# MICROCONTROLLER.net
KiCad netlist of a schematic drawn in Altium Designer
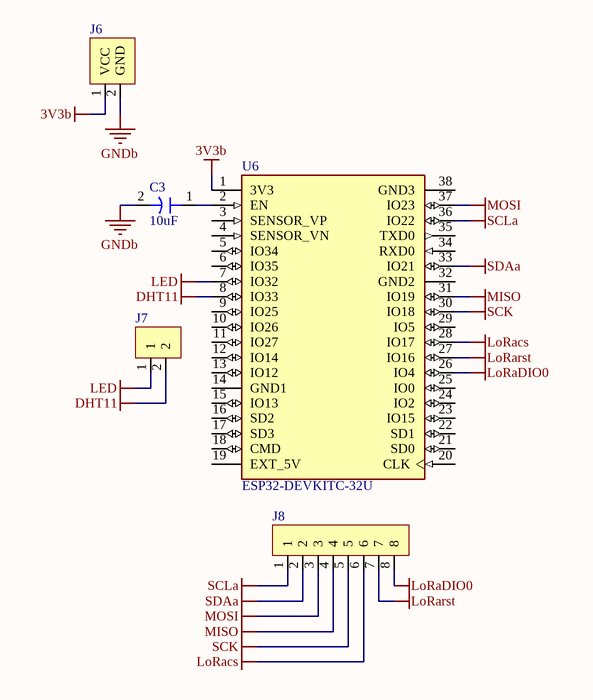
[diagram p0: MICROCONTROLLER.SchDoc]

(export (version "E")
  (design (tool "Eeschema 10.0.6"))
  (components
    (comp (ref "C3")
      (value "10uF")
      (footprint "Electrolytic capacitor 2mm")
      (description "Throug-hole 10uF")
      (libsource (lib "CanSat1_SchLib") (part "E_CAP_10uF"))
    )
    (comp (ref "J6")
      (value "PWR_CONNECTOR")
      (footprint "BATT")
      (description "THT Connector")
      (libsource (lib "CanSat1_SchLib") (part "PWR-CONN"))
    )
    (comp (ref "J7")
      (value "2x1_CONN")
      (footprint "CONN2x1_2.54mm")
      (description "THT 2x1 2.54mm CONN")
      (libsource (lib "CanSat1_SchLib") (part "CONN 2x1"))
    )
    (comp (ref "J8")
      (value "8x1 CONN")
      (footprint "CONN8x1_2.54")
      (description "THT 8x1 2.54mm CONN")
      (libsource (lib "CanSat1_SchLib") (part "CONN 8x1"))
    )
    (comp (ref "U6")
      (value "ESP32-DEVKITC-32U")
      (footprint "MODULE_ESP32-DEVKITC-32U")
      (fields (field (name "MF") "Espressif Systems"))
      (libsource (lib "CanSat1_SchLib") (part "ESP32-DEVKITC-32U"))
    )
  )
  (nets
    (net (code "1") (name "3V3b") (class "Default")
      (node (ref "J6") (pin "1") (pinfunction "VCC_1") (pintype "passive"))
      (node (ref "U6") (pin "1") (pinfunction "3V3_1") (pintype "power_in"))
    )
    (net (code "2") (name "DHT11") (class "Default")
      (node (ref "J7") (pin "2") (pinfunction "2_2") (pintype "passive"))
      (node (ref "U6") (pin "8") (pinfunction "IO33_8") (pintype "bidirectional"))
    )
    (net (code "3") (name "GNDb") (class "Default")
      (node (ref "C3") (pin "2") (pinfunction "-_2") (pintype "passive"))
      (node (ref "J6") (pin "2") (pinfunction "GND_2") (pintype "passive"))
    )
    (net (code "4") (name "LED") (class "Default")
      (node (ref "J7") (pin "1") (pinfunction "1_1") (pintype "passive"))
      (node (ref "U6") (pin "7") (pinfunction "IO32_7") (pintype "bidirectional"))
    )
    (net (code "5") (name "LoRaDIO0") (class "Default")
      (node (ref "J8") (pin "8") (pinfunction "8_8") (pintype "passive"))
      (node (ref "U6") (pin "26") (pinfunction "IO4_26") (pintype "bidirectional"))
    )
    (net (code "6") (name "LoRacs") (class "Default")
      (node (ref "J8") (pin "6") (pinfunction "6_6") (pintype "passive"))
      (node (ref "U6") (pin "28") (pinfunction "IO17_28") (pintype "bidirectional"))
    )
    (net (code "7") (name "LoRarst") (class "Default")
      (node (ref "J8") (pin "7") (pinfunction "7_7") (pintype "passive"))
      (node (ref "U6") (pin "27") (pinfunction "IO16_27") (pintype "bidirectional"))
    )
    (net (code "8") (name "MISO") (class "Default")
      (node (ref "J8") (pin "4") (pinfunction "4_4") (pintype "passive"))
      (node (ref "U6") (pin "31") (pinfunction "IO19_31") (pintype "bidirectional"))
    )
    (net (code "9") (name "MOSI") (class "Default")
      (node (ref "J8") (pin "3") (pinfunction "3_3") (pintype "passive"))
      (node (ref "U6") (pin "37") (pinfunction "IO23_37") (pintype "bidirectional"))
    )
    (net (code "10") (name "Net-(C3-+)") (class "Default")
      (node (ref "C3") (pin "1") (pinfunction "+_1") (pintype "passive"))
      (node (ref "U6") (pin "2") (pinfunction "EN_2") (pintype "input"))
    )
    (net (code "11") (name "SCK") (class "Default")
      (node (ref "J8") (pin "5") (pinfunction "5_5") (pintype "passive"))
      (node (ref "U6") (pin "30") (pinfunction "IO18_30") (pintype "bidirectional"))
    )
    (net (code "12") (name "SCLa") (class "Default")
      (node (ref "J8") (pin "1") (pinfunction "1_1") (pintype "passive"))
      (node (ref "U6") (pin "36") (pinfunction "IO22_36") (pintype "bidirectional"))
    )
    (net (code "13") (name "SDAa") (class "Default")
      (node (ref "J8") (pin "2") (pinfunction "2_2") (pintype "passive"))
      (node (ref "U6") (pin "33") (pinfunction "IO21_33") (pintype "bidirectional"))
    )
    (net (code "14") (name "unconnected-(U6-CLK-Pad20)") (class "Default")
      (node (ref "U6") (pin "20") (pinfunction "CLK_20") (pintype "input"))
    )
    (net (code "15") (name "unconnected-(U6-CMD-Pad18)") (class "Default")
      (node (ref "U6") (pin "18") (pinfunction "CMD_18") (pintype "bidirectional"))
    )
    (net (code "16") (name "unconnected-(U6-EXT_5V-Pad19)") (class "Default")
      (node (ref "U6") (pin "19") (pinfunction "EXT_5V_19") (pintype "power_in"))
    )
    (net (code "17") (name "unconnected-(U6-GND1-Pad14)") (class "Default")
      (node (ref "U6") (pin "14") (pinfunction "GND1_14") (pintype "power_in"))
    )
    (net (code "18") (name "unconnected-(U6-GND2-Pad32)") (class "Default")
      (node (ref "U6") (pin "32") (pinfunction "GND2_32") (pintype "power_in"))
    )
    (net (code "19") (name "unconnected-(U6-GND3-Pad38)") (class "Default")
      (node (ref "U6") (pin "38") (pinfunction "GND3_38") (pintype "power_in"))
    )
    (net (code "20") (name "unconnected-(U6-IO0-Pad25)") (class "Default")
      (node (ref "U6") (pin "25") (pinfunction "IO0_25") (pintype "bidirectional"))
    )
    (net (code "21") (name "unconnected-(U6-IO2-Pad24)") (class "Default")
      (node (ref "U6") (pin "24") (pinfunction "IO2_24") (pintype "bidirectional"))
    )
    (net (code "22") (name "unconnected-(U6-IO5-Pad29)") (class "Default")
      (node (ref "U6") (pin "29") (pinfunction "IO5_29") (pintype "bidirectional"))
    )
    (net (code "23") (name "unconnected-(U6-IO12-Pad13)") (class "Default")
      (node (ref "U6") (pin "13") (pinfunction "IO12_13") (pintype "bidirectional"))
    )
    (net (code "24") (name "unconnected-(U6-IO13-Pad15)") (class "Default")
      (node (ref "U6") (pin "15") (pinfunction "IO13_15") (pintype "bidirectional"))
    )
    (net (code "25") (name "unconnected-(U6-IO14-Pad12)") (class "Default")
      (node (ref "U6") (pin "12") (pinfunction "IO14_12") (pintype "bidirectional"))
    )
    (net (code "26") (name "unconnected-(U6-IO15-Pad23)") (class "Default")
      (node (ref "U6") (pin "23") (pinfunction "IO15_23") (pintype "bidirectional"))
    )
    (net (code "27") (name "unconnected-(U6-IO25-Pad9)") (class "Default")
      (node (ref "U6") (pin "9") (pinfunction "IO25_9") (pintype "bidirectional"))
    )
    (net (code "28") (name "unconnected-(U6-IO26-Pad10)") (class "Default")
      (node (ref "U6") (pin "10") (pinfunction "IO26_10") (pintype "bidirectional"))
    )
    (net (code "29") (name "unconnected-(U6-IO27-Pad11)") (class "Default")
      (node (ref "U6") (pin "11") (pinfunction "IO27_11") (pintype "bidirectional"))
    )
    (net (code "30") (name "unconnected-(U6-IO34-Pad5)") (class "Default")
      (node (ref "U6") (pin "5") (pinfunction "IO34_5") (pintype "bidirectional"))
    )
    (net (code "31") (name "unconnected-(U6-IO35-Pad6)") (class "Default")
      (node (ref "U6") (pin "6") (pinfunction "IO35_6") (pintype "bidirectional"))
    )
    (net (code "32") (name "unconnected-(U6-RXD0-Pad34)") (class "Default")
      (node (ref "U6") (pin "34") (pinfunction "RXD0_34") (pintype "input"))
    )
    (net (code "33") (name "unconnected-(U6-SD0-Pad21)") (class "Default")
      (node (ref "U6") (pin "21") (pinfunction "SD0_21") (pintype "bidirectional"))
    )
    (net (code "34") (name "unconnected-(U6-SD1-Pad22)") (class "Default")
      (node (ref "U6") (pin "22") (pinfunction "SD1_22") (pintype "bidirectional"))
    )
    (net (code "35") (name "unconnected-(U6-SD2-Pad16)") (class "Default")
      (node (ref "U6") (pin "16") (pinfunction "SD2_16") (pintype "bidirectional"))
    )
    (net (code "36") (name "unconnected-(U6-SD3-Pad17)") (class "Default")
      (node (ref "U6") (pin "17") (pinfunction "SD3_17") (pintype "bidirectional"))
    )
    (net (code "37") (name "unconnected-(U6-SENSOR_VN-Pad4)") (class "Default")
      (node (ref "U6") (pin "4") (pinfunction "SENSOR_VN_4") (pintype "input"))
    )
    (net (code "38") (name "unconnected-(U6-SENSOR_VP-Pad3)") (class "Default")
      (node (ref "U6") (pin "3") (pinfunction "SENSOR_VP_3") (pintype "input"))
    )
    (net (code "39") (name "unconnected-(U6-TXD0-Pad35)") (class "Default")
      (node (ref "U6") (pin "35") (pinfunction "TXD0_35") (pintype "output"))
    )
  )
)
